# UC3844_-_CON_TEST.net
KiCad netlist of a schematic drawn in Altium Designer
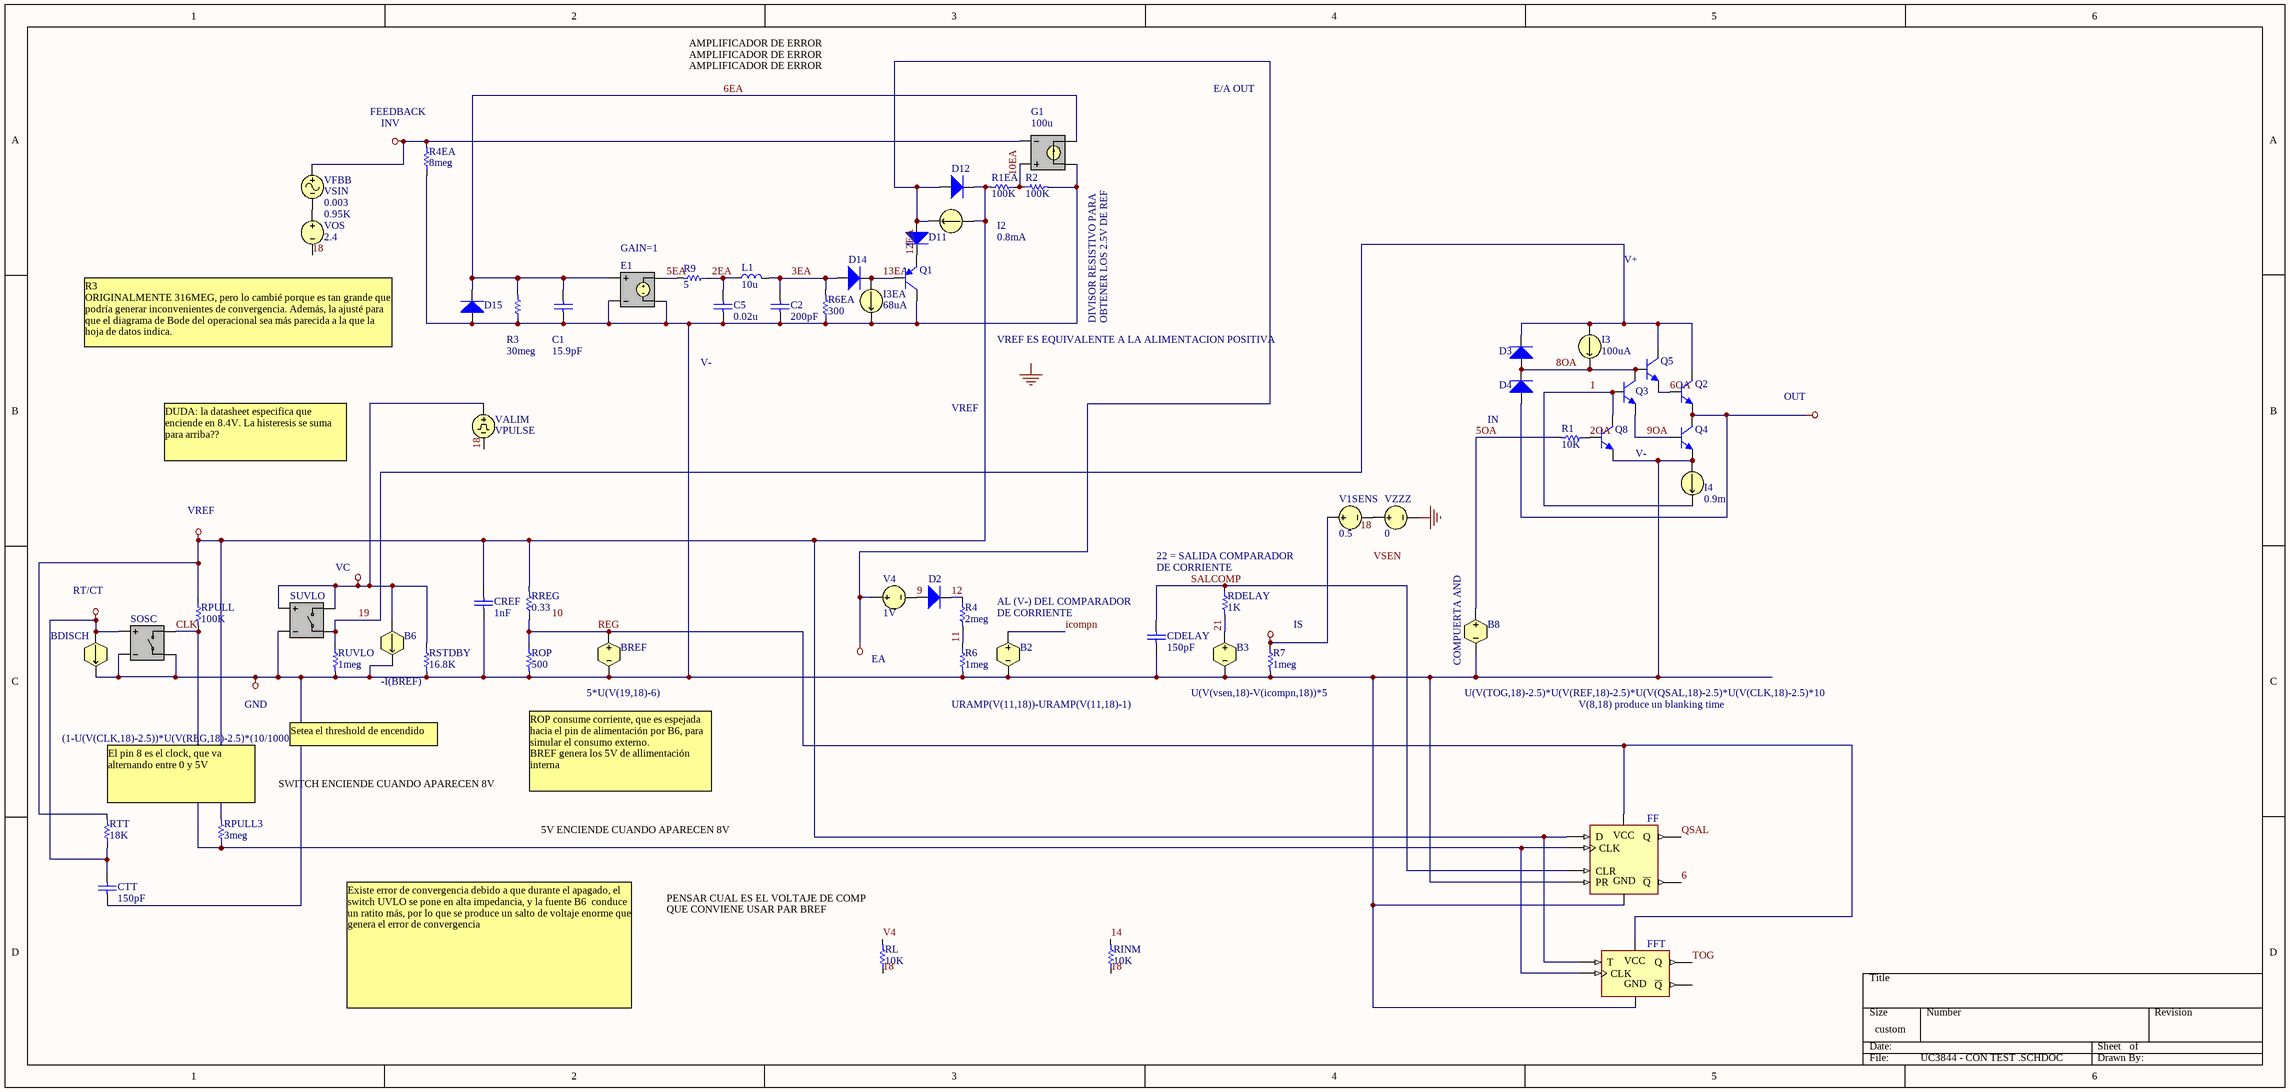
[diagram p0: UC3844 - CON TEST .SCHDOC]

(export (version "E")
  (design (tool "Eeschema 10.0.6"))
  (components
    (comp (ref "B2")
      (value "BVSRC")
      (description "Non-Linear Dependent Voltage Source")
      (fields
        (field (name "EQUATION") "URAMP(V(11,18))-URAMP(V(11,18)-1)")
        (field (name "PUBLISHER") "Altium Limited")
      )
      (libsource (lib "Simulation Sources") (part "BVSRC"))
    )
    (comp (ref "B3")
      (value "BVSRC")
      (description "Non-Linear Dependent Voltage Source")
      (fields
        (field (name "EQUATION") "U(V(vsen,18)-V(icompn,18))*5")
        (field (name "PUBLISHER") "Altium Limited")
      )
      (libsource (lib "Simulation Sources") (part "BVSRC"))
    )
    (comp (ref "B6")
      (value "BISRC")
      (description "Non-Linear Dependent Current Source")
      (fields (field (name "EQUATION") "-I(BREF)") (field (name "PUBLISHER") "Altium Limited"))
      (libsource (lib "Simulation Sources") (part "BISRC"))
    )
    (comp (ref "B8")
      (value "BVSRC")
      (description "Non-Linear Dependent Voltage Source")
      (fields
        (field (name "EQUATION") "U(V(TOG,18)-2.5)*U(V(REF,18)-2.5)*U(V(QSAL,18)-2.5)*U(V(CLK,18)-2.5)*10")
        (field (name "PUBLISHER") "Altium Limited")
      )
      (libsource (lib "Simulation Sources") (part "BVSRC"))
    )
    (comp (ref "BDISCH")
      (value "BISRC")
      (description "Non-Linear Dependent Current Source")
      (fields
        (field (name "EQUATION") "(1-U(V(CLK,18)-2.5))*U(V(REG,18)-2.5)*(10/1000)")
        (field (name "PUBLISHER") "Altium Limited")
      )
      (libsource (lib "Simulation Sources") (part "BISRC"))
    )
    (comp (ref "BREF")
      (value "BVSRC")
      (description "Non-Linear Dependent Voltage Source")
      (fields (field (name "EQUATION") "5*U(V(19,18)-6)") (field (name "PUBLISHER") "Altium Limited"))
      (libsource (lib "Simulation Sources") (part "BVSRC"))
    )
    (comp (ref "C1")
      (value "15.9pF")
      (footprint "0805")
      (description "Capacitor")
      (fields (field (name "VOLTAGE") "50V") (field (name "Comment") "Cap"))
      (libsource (lib "FEDE") (part "Cap"))
    )
    (comp (ref "C2")
      (value "200pF")
      (footprint "0805")
      (description "Capacitor")
      (fields (field (name "VOLTAGE") "50V") (field (name "Comment") "Cap"))
      (libsource (lib "FEDE") (part "Cap"))
    )
    (comp (ref "C5")
      (value "0.02u")
      (footprint "0805")
      (description "Capacitor")
      (fields (field (name "VOLTAGE") "50V") (field (name "Comment") "Cap"))
      (libsource (lib "FEDE") (part "Cap"))
    )
    (comp (ref "CDELAY")
      (value "150pF")
      (footprint "0805")
      (description "Capacitor")
      (fields (field (name "VOLTAGE") "50V") (field (name "Comment") "Cap"))
      (libsource (lib "FEDE") (part "Cap"))
    )
    (comp (ref "CREF")
      (value "1nF")
      (footprint "0805")
      (description "Capacitor")
      (fields (field (name "VOLTAGE") "50V") (field (name "Comment") "Cap"))
      (libsource (lib "FEDE") (part "Cap"))
    )
    (comp (ref "CTT")
      (value "150pF")
      (footprint "0805")
      (description "Capacitor")
      (fields (field (name "VOLTAGE") "50V") (field (name "Comment") "Cap"))
      (libsource (lib "FEDE") (part "Cap"))
    )
    (comp (ref "D2")
      (value "Diode")
      (footprint "diode400")
      (description "Diodo")
      (libsource (lib "FEDE") (part "Diode"))
    )
    (comp (ref "D3")
      (value "Diode")
      (footprint "diode400")
      (description "Diodo")
      (libsource (lib "FEDE") (part "Diode"))
    )
    (comp (ref "D4")
      (value "Diode")
      (footprint "diode400")
      (description "Diodo")
      (libsource (lib "FEDE") (part "Diode"))
    )
    (comp (ref "D11")
      (value "Diode")
      (footprint "diode400")
      (description "Diodo")
      (libsource (lib "FEDE") (part "Diode"))
    )
    (comp (ref "D12")
      (value "Diode")
      (footprint "diode400")
      (description "Diodo")
      (libsource (lib "FEDE") (part "Diode"))
    )
    (comp (ref "D14")
      (value "Diode")
      (footprint "diode400")
      (description "Diodo")
      (libsource (lib "FEDE") (part "Diode"))
    )
    (comp (ref "D15")
      (value "Diode")
      (footprint "diode400")
      (description "Diodo")
      (libsource (lib "FEDE") (part "Diode"))
    )
    (comp (ref "E1")
      (value "ESRC")
      (description "Voltage Controlled Voltage Source")
      (fields (field (name "PUBLISHER") "Altium Limited"))
      (libsource (lib "Simulation Sources") (part "ESRC"))
    )
    (comp (ref "FF")
      (value "FFSRV2")
      (description "D-Type Positive-Edge-Triggered Flip-Flop with Clear and Preset (simulación)")
      (libsource (lib "FEDE") (part "FFSRV2"))
    )
    (comp (ref "FFT")
      (value "FFT")
      (description "Positive-Edge-Triggered Flip-Flop T (simulación)")
      (libsource (lib "FEDE") (part "FFT"))
    )
    (comp (ref "G1")
      (value "GSRC")
      (description "Voltage Controlled Current Source")
      (fields (field (name "GAIN") "100u") (field (name "PUBLISHER") "Altium Limited"))
      (libsource (lib "Simulation Sources") (part "GSRC"))
    )
    (comp (ref "I2")
      (value "0.8mA")
      (description "Current Source")
      (fields (field (name "Comment") "ISRC") (field (name "PUBLISHER") "Altium Limited"))
      (libsource (lib "Simulation Sources") (part "ISRC"))
    )
    (comp (ref "I3")
      (value "100uA")
      (description "Current Source")
      (fields (field (name "Comment") "ISRC") (field (name "PUBLISHER") "Altium Limited"))
      (libsource (lib "Simulation Sources") (part "ISRC"))
    )
    (comp (ref "I3EA")
      (value "68uA")
      (description "Current Source")
      (fields (field (name "Comment") "ISRC") (field (name "PUBLISHER") "Altium Limited"))
      (libsource (lib "Simulation Sources") (part "ISRC"))
    )
    (comp (ref "I4")
      (value "0.9m")
      (description "Current Source")
      (fields (field (name "Comment") "ISRC") (field (name "PUBLISHER") "Altium Limited"))
      (libsource (lib "Simulation Sources") (part "ISRC"))
    )
    (comp (ref "L1")
      (value "10u")
      (footprint "TOROIDE TN14-9-5")
      (description "Inductor")
      (fields (field (name "Comment") "Inductor2"))
      (libsource (lib "FEDE") (part "Inductor2"))
    )
    (comp (ref "Q1")
      (value "PNP")
      (footprint "SOT23")
      (description "PNP Bipolar Transistor")
      (libsource (lib "FEDE") (part "PNP"))
    )
    (comp (ref "Q2")
      (value "NPN")
      (footprint "SOT23")
      (description "NPN Bipolar Transistor")
      (libsource (lib "FEDE") (part "NPN"))
    )
    (comp (ref "Q3")
      (value "NPN")
      (footprint "SOT23")
      (description "NPN Bipolar Transistor")
      (libsource (lib "FEDE") (part "NPN"))
    )
    (comp (ref "Q4")
      (value "NPN")
      (footprint "SOT23")
      (description "NPN Bipolar Transistor")
      (libsource (lib "FEDE") (part "NPN"))
    )
    (comp (ref "Q5")
      (value "NPN")
      (footprint "SOT23")
      (description "NPN Bipolar Transistor")
      (libsource (lib "FEDE") (part "NPN"))
    )
    (comp (ref "Q8")
      (value "NPN")
      (footprint "SOT23")
      (description "NPN Bipolar Transistor")
      (libsource (lib "FEDE") (part "NPN"))
    )
    (comp (ref "R1")
      (value "10K")
      (footprint "0805")
      (description "Resistor")
      (fields (field (name "POWER") "0.25W") (field (name "Comment") "Res"))
      (libsource (lib "FEDE") (part "Res"))
    )
    (comp (ref "R1EA")
      (value "100K")
      (footprint "0805")
      (description "Resistor")
      (fields (field (name "POWER") "0.25W") (field (name "Comment") "Res"))
      (libsource (lib "FEDE") (part "Res"))
    )
    (comp (ref "R2")
      (value "100K")
      (footprint "0805")
      (description "Resistor")
      (fields (field (name "POWER") "0.25W") (field (name "Comment") "Res"))
      (libsource (lib "FEDE") (part "Res"))
    )
    (comp (ref "R3")
      (value "30meg")
      (footprint "0805")
      (description "Resistor")
      (fields (field (name "POWER") "0.25W") (field (name "Comment") "Res"))
      (libsource (lib "FEDE") (part "Res"))
    )
    (comp (ref "R4")
      (value "2meg")
      (footprint "0805")
      (description "Resistor")
      (fields (field (name "POWER") "0.25W") (field (name "Comment") "Res"))
      (libsource (lib "FEDE") (part "Res"))
    )
    (comp (ref "R4EA")
      (value "8meg")
      (footprint "0805")
      (description "Resistor")
      (fields (field (name "POWER") "0.25W") (field (name "Comment") "Res"))
      (libsource (lib "FEDE") (part "Res"))
    )
    (comp (ref "R6")
      (value "1meg")
      (footprint "0805")
      (description "Resistor")
      (fields (field (name "POWER") "0.25W") (field (name "Comment") "Res"))
      (libsource (lib "FEDE") (part "Res"))
    )
    (comp (ref "R6EA")
      (value "300")
      (footprint "0805")
      (description "Resistor")
      (fields (field (name "POWER") "0.25W") (field (name "Comment") "Res"))
      (libsource (lib "FEDE") (part "Res"))
    )
    (comp (ref "R7")
      (value "1meg")
      (footprint "0805")
      (description "Resistor")
      (fields (field (name "POWER") "0.25W") (field (name "Comment") "Res"))
      (libsource (lib "FEDE") (part "Res"))
    )
    (comp (ref "R9")
      (value "5")
      (footprint "0805")
      (description "Resistor")
      (fields (field (name "POWER") "0.25W") (field (name "Comment") "Res"))
      (libsource (lib "FEDE") (part "Res"))
    )
    (comp (ref "RDELAY")
      (value "1K")
      (footprint "0805")
      (description "Resistor")
      (fields (field (name "POWER") "0.25W") (field (name "Comment") "Res"))
      (libsource (lib "FEDE") (part "Res"))
    )
    (comp (ref "RINM")
      (value "10K")
      (footprint "0805")
      (description "Resistor")
      (fields (field (name "POWER") "0.25W") (field (name "Comment") "Res"))
      (libsource (lib "FEDE") (part "Res"))
    )
    (comp (ref "RL")
      (value "10K")
      (footprint "0805")
      (description "Resistor")
      (fields (field (name "POWER") "0.25W") (field (name "Comment") "Res"))
      (libsource (lib "FEDE") (part "Res"))
    )
    (comp (ref "ROP")
      (value "500")
      (footprint "0805")
      (description "Resistor")
      (fields (field (name "POWER") "0.25W") (field (name "Comment") "Res"))
      (libsource (lib "FEDE") (part "Res"))
    )
    (comp (ref "RPULL")
      (value "100K")
      (footprint "0805")
      (description "Resistor")
      (fields (field (name "POWER") "0.25W") (field (name "Comment") "Res"))
      (libsource (lib "FEDE") (part "Res"))
    )
    (comp (ref "RPULL3")
      (value "3meg")
      (footprint "0805")
      (description "Resistor")
      (fields (field (name "POWER") "0.25W") (field (name "Comment") "Res"))
      (libsource (lib "FEDE") (part "Res"))
    )
    (comp (ref "RREG")
      (value "0.33")
      (footprint "0805")
      (description "Resistor")
      (fields (field (name "POWER") "0.25W") (field (name "Comment") "Res"))
      (libsource (lib "FEDE") (part "Res"))
    )
    (comp (ref "RSTDBY")
      (value "16.8K")
      (footprint "0805")
      (description "Resistor")
      (fields (field (name "POWER") "0.25W") (field (name "Comment") "Res"))
      (libsource (lib "FEDE") (part "Res"))
    )
    (comp (ref "RTT")
      (value "18K")
      (footprint "0805")
      (description "Resistor")
      (fields (field (name "POWER") "0.25W") (field (name "Comment") "Res"))
      (libsource (lib "FEDE") (part "Res"))
    )
    (comp (ref "RUVLO")
      (value "1meg")
      (footprint "0805")
      (description "Resistor")
      (fields (field (name "POWER") "0.25W") (field (name "Comment") "Res"))
      (libsource (lib "FEDE") (part "Res"))
    )
    (comp (ref "SOSC")
      (value "VSW")
      (description "Voltage Controlled Switch (simulación)")
      (libsource (lib "FEDE") (part "VSW"))
    )
    (comp (ref "SUVLO")
      (value "VSW")
      (description "Voltage Controlled Switch (simulación)")
      (libsource (lib "FEDE") (part "VSW"))
    )
    (comp (ref "V1SENS")
      (value "0.5")
      (description "Voltage Source")
      (fields (field (name "Comment") "VSRC") (field (name "PUBLISHER") "Altium Limited"))
      (libsource (lib "Simulation Sources") (part "VSRC"))
    )
    (comp (ref "V4")
      (value "1V")
      (description "Voltage Source")
      (fields (field (name "Comment") "VSRC") (field (name "PUBLISHER") "Altium Limited"))
      (libsource (lib "Simulation Sources") (part "VSRC"))
    )
    (comp (ref "VALIM")
      (value "VPULSE")
      (description "Pulse Voltage Source")
      (fields (field (name "PUBLISHER") "Altium Limited"))
      (libsource (lib "Simulation Sources") (part "VPULSE"))
    )
    (comp (ref "VFBB")
      (value "VSIN")
      (description "Sinusoidal Voltage Source")
      (fields
        (field (name "AMPLITUDE") "0.003")
        (field (name "FREQUENCY") "0.95K")
        (field (name "PUBLISHER") "Altium Limited")
      )
      (libsource (lib "Simulation Sources") (part "VSIN"))
    )
    (comp (ref "VOS")
      (value "2.4")
      (description "Voltage Source")
      (fields (field (name "Comment") "VSRC") (field (name "PUBLISHER") "Altium Limited"))
      (libsource (lib "Simulation Sources") (part "VSRC"))
    )
    (comp (ref "VZZZ")
      (value "0")
      (description "Voltage Source")
      (fields (field (name "Comment") "VSRC") (field (name "PUBLISHER") "Altium Limited"))
      (libsource (lib "Simulation Sources") (part "VSRC"))
    )
  )
  (nets
    (net (code "1") (name "/1") (class "Default")
      (node (ref "I4") (pin "2") (pinfunction "2_2") (pintype "passive"))
      (node (ref "Q3") (pin "2") (pinfunction "B_2") (pintype "passive"))
      (node (ref "Q8") (pin "1") (pinfunction "C_1") (pintype "passive"))
    )
    (net (code "2") (name "/2EA") (class "Default")
      (node (ref "C5") (pin "2") (pinfunction "2_2") (pintype "passive"))
      (node (ref "L1") (pin "1") (pinfunction "1_1") (pintype "passive"))
      (node (ref "R9") (pin "1") (pinfunction "1_1") (pintype "passive"))
    )
    (net (code "3") (name "/2OA") (class "Default")
      (node (ref "Q8") (pin "2") (pinfunction "B_2") (pintype "passive"))
      (node (ref "R1") (pin "1") (pinfunction "1_1") (pintype "passive"))
    )
    (net (code "4") (name "/3EA") (class "Default")
      (node (ref "C2") (pin "2") (pinfunction "2_2") (pintype "passive"))
      (node (ref "D14") (pin "1") (pinfunction "1_1") (pintype "passive"))
      (node (ref "L1") (pin "2") (pinfunction "2_2") (pintype "passive"))
      (node (ref "R6EA") (pin "2") (pinfunction "2_2") (pintype "passive"))
    )
    (net (code "5") (name "/5EA") (class "Default")
      (node (ref "E1") (pin "3") (pinfunction "N+_3") (pintype "passive"))
      (node (ref "R9") (pin "2") (pinfunction "2_2") (pintype "passive"))
    )
    (net (code "6") (name "/5OA") (class "Default")
      (node (ref "B8") (pin "1") (pinfunction "1_1") (pintype "passive"))
      (node (ref "R1") (pin "2") (pinfunction "2_2") (pintype "passive"))
    )
    (net (code "7") (name "/6") (class "Default")
      (node (ref "FF") (pin "6") (pinfunction "~{Q}_6") (pintype "output"))
    )
    (net (code "8") (name "/6EA") (class "Default")
      (node (ref "C1") (pin "2") (pinfunction "2_2") (pintype "passive"))
      (node (ref "D15") (pin "2") (pinfunction "2_2") (pintype "passive"))
      (node (ref "E1") (pin "1") (pinfunction "NC+_1") (pintype "passive"))
      (node (ref "G1") (pin "4") (pinfunction "N-_4") (pintype "passive"))
      (node (ref "R3") (pin "2") (pinfunction "2_2") (pintype "passive"))
    )
    (net (code "9") (name "/6OA") (class "Default")
      (node (ref "Q2") (pin "2") (pinfunction "B_2") (pintype "passive"))
      (node (ref "Q5") (pin "3") (pinfunction "E_3") (pintype "passive"))
    )
    (net (code "10") (name "/8OA") (class "Default")
      (node (ref "D3") (pin "1") (pinfunction "1_1") (pintype "passive"))
      (node (ref "D4") (pin "2") (pinfunction "2_2") (pintype "passive"))
      (node (ref "I3") (pin "2") (pinfunction "2_2") (pintype "passive"))
      (node (ref "Q3") (pin "1") (pinfunction "C_1") (pintype "passive"))
      (node (ref "Q5") (pin "2") (pinfunction "B_2") (pintype "passive"))
    )
    (net (code "11") (name "/9") (class "Default")
      (node (ref "D2") (pin "1") (pinfunction "1_1") (pintype "passive"))
      (node (ref "V4") (pin "2") (pinfunction "2_2") (pintype "passive"))
    )
    (net (code "12") (name "/9OA") (class "Default")
      (node (ref "Q3") (pin "3") (pinfunction "E_3") (pintype "passive"))
      (node (ref "Q4") (pin "2") (pinfunction "B_2") (pintype "passive"))
    )
    (net (code "14") (name "/10EA") (class "Default")
      (node (ref "G1") (pin "1") (pinfunction "NC+_1") (pintype "passive"))
      (node (ref "R1EA") (pin "1") (pinfunction "1_1") (pintype "passive"))
      (node (ref "R2") (pin "1") (pinfunction "1_1") (pintype "passive"))
    )
    (net (code "15") (name "/11") (class "Default")
      (node (ref "R4") (pin "2") (pinfunction "2_2") (pintype "passive"))
      (node (ref "R6") (pin "1") (pinfunction "1_1") (pintype "passive"))
    )
    (net (code "16") (name "/12") (class "Default")
      (node (ref "D2") (pin "2") (pinfunction "2_2") (pintype "passive"))
      (node (ref "R4") (pin "1") (pinfunction "1_1") (pintype "passive"))
    )
    (net (code "17") (name "/12EA") (class "Default")
      (node (ref "D11") (pin "2") (pinfunction "2_2") (pintype "passive"))
      (node (ref "Q1") (pin "3") (pinfunction "E_3") (pintype "passive"))
    )
    (net (code "18") (name "/13EA") (class "Default")
      (node (ref "D14") (pin "2") (pinfunction "2_2") (pintype "passive"))
      (node (ref "I3EA") (pin "1") (pinfunction "1_1") (pintype "passive"))
      (node (ref "Q1") (pin "2") (pinfunction "B_2") (pintype "passive"))
    )
    (net (code "19") (name "/14") (class "Default")
      (node (ref "RINM") (pin "2") (pinfunction "2_2") (pintype "passive"))
    )
    (net (code "20") (name "/19") (class "Default")
      (node (ref "D3") (pin "2") (pinfunction "2_2") (pintype "passive"))
      (node (ref "I3") (pin "1") (pinfunction "1_1") (pintype "passive"))
      (node (ref "Q2") (pin "1") (pinfunction "C_1") (pintype "passive"))
      (node (ref "Q5") (pin "1") (pinfunction "C_1") (pintype "passive"))
      (node (ref "RUVLO") (pin "1") (pinfunction "1_1") (pintype "passive"))
      (node (ref "SUVLO") (pin "4") (pinfunction "N2-_4") (pintype "passive"))
    )
    (net (code "21") (name "/21") (class "Default")
      (node (ref "B3") (pin "1") (pinfunction "1_1") (pintype "passive"))
      (node (ref "RDELAY") (pin "2") (pinfunction "2_2") (pintype "passive"))
    )
    (net (code "22") (name "/CLK") (class "Default")
      (node (ref "FF") (pin "3") (pinfunction "CLK_3") (pintype "input"))
      (node (ref "FFT") (pin "2") (pinfunction "CLK_2") (pintype "input"))
      (node (ref "RPULL") (pin "2") (pinfunction "2_2") (pintype "passive"))
      (node (ref "RPULL3") (pin "1") (pinfunction "1_1") (pintype "passive"))
      (node (ref "SOSC") (pin "3") (pinfunction "N2+_3") (pintype "passive"))
    )
    (net (code "23") (name "/QSAL") (class "Default")
      (node (ref "FF") (pin "5") (pinfunction "Q_5") (pintype "output"))
    )
    (net (code "24") (name "/REG") (class "Default")
      (node (ref "BREF") (pin "1") (pinfunction "1_1") (pintype "passive"))
      (node (ref "FF") (pin "14") (pinfunction "VCC_14") (pintype "power_in"))
      (node (ref "FFT") (pin "5") (pinfunction "VCC_5") (pintype "power_in"))
      (node (ref "ROP") (pin "1") (pinfunction "1_1") (pintype "passive"))
      (node (ref "RREG") (pin "1") (pinfunction "1_1") (pintype "passive"))
    )
    (net (code "25") (name "/SALCOMP") (class "Default")
      (node (ref "CDELAY") (pin "2") (pinfunction "2_2") (pintype "passive"))
      (node (ref "FF") (pin "1") (pinfunction "CLR_1") (pintype "input"))
      (node (ref "RDELAY") (pin "1") (pinfunction "1_1") (pintype "passive"))
    )
    (net (code "26") (name "/TOG") (class "Default")
      (node (ref "FFT") (pin "3") (pinfunction "Q_3") (pintype "output"))
    )
    (net (code "27") (name "/V4") (class "Default")
      (node (ref "RL") (pin "2") (pinfunction "2_2") (pintype "passive"))
    )
    (net (code "28") (name "/icompn") (class "Default")
      (node (ref "B2") (pin "1") (pinfunction "1_1") (pintype "passive"))
    )
    (net (code "29") (name "18") (class "Default")
      (node (ref "B2") (pin "2") (pinfunction "2_2") (pintype "passive"))
      (node (ref "B3") (pin "2") (pinfunction "2_2") (pintype "passive"))
      (node (ref "B6") (pin "2") (pinfunction "2_2") (pintype "passive"))
      (node (ref "B8") (pin "2") (pinfunction "2_2") (pintype "passive"))
      (node (ref "BDISCH") (pin "2") (pinfunction "2_2") (pintype "passive"))
      (node (ref "BREF") (pin "2") (pinfunction "2_2") (pintype "passive"))
      (node (ref "C1") (pin "1") (pinfunction "1_1") (pintype "passive"))
      (node (ref "C2") (pin "1") (pinfunction "1_1") (pintype "passive"))
      (node (ref "C5") (pin "1") (pinfunction "1_1") (pintype "passive"))
      (node (ref "CDELAY") (pin "1") (pinfunction "1_1") (pintype "passive"))
      (node (ref "CREF") (pin "1") (pinfunction "1_1") (pintype "passive"))
      (node (ref "CTT") (pin "1") (pinfunction "1_1") (pintype "passive"))
      (node (ref "D15") (pin "1") (pinfunction "1_1") (pintype "passive"))
      (node (ref "E1") (pin "2") (pinfunction "NC-_2") (pintype "passive"))
      (node (ref "E1") (pin "4") (pinfunction "N-_4") (pintype "passive"))
      (node (ref "FF") (pin "4") (pinfunction "PR_4") (pintype "input"))
      (node (ref "FF") (pin "7") (pinfunction "GND_7") (pintype "power_in"))
      (node (ref "FFT") (pin "6") (pinfunction "GND_6") (pintype "power_in"))
      (node (ref "G1") (pin "3") (pinfunction "N+_3") (pintype "passive"))
      (node (ref "I3EA") (pin "2") (pinfunction "2_2") (pintype "passive"))
      (node (ref "I4") (pin "1") (pinfunction "1_1") (pintype "passive"))
      (node (ref "Q1") (pin "1") (pinfunction "C_1") (pintype "passive"))
      (node (ref "Q4") (pin "3") (pinfunction "E_3") (pintype "passive"))
      (node (ref "Q8") (pin "3") (pinfunction "E_3") (pintype "passive"))
      (node (ref "R2") (pin "2") (pinfunction "2_2") (pintype "passive"))
      (node (ref "R3") (pin "1") (pinfunction "1_1") (pintype "passive"))
      (node (ref "R4EA") (pin "1") (pinfunction "1_1") (pintype "passive"))
      (node (ref "R6") (pin "2") (pinfunction "2_2") (pintype "passive"))
      (node (ref "R6EA") (pin "1") (pinfunction "1_1") (pintype "passive"))
      (node (ref "R7") (pin "2") (pinfunction "2_2") (pintype "passive"))
      (node (ref "RINM") (pin "1") (pinfunction "1_1") (pintype "passive"))
      (node (ref "RL") (pin "1") (pinfunction "1_1") (pintype "passive"))
      (node (ref "ROP") (pin "2") (pinfunction "2_2") (pintype "passive"))
      (node (ref "RSTDBY") (pin "2") (pinfunction "2_2") (pintype "passive"))
      (node (ref "RUVLO") (pin "2") (pinfunction "2_2") (pintype "passive"))
      (node (ref "SOSC") (pin "2") (pinfunction "N1-_2") (pintype "passive"))
      (node (ref "SOSC") (pin "4") (pinfunction "N2-_4") (pintype "passive"))
      (node (ref "SUVLO") (pin "2") (pinfunction "N1-_2") (pintype "passive"))
      (node (ref "V1SENS") (pin "2") (pinfunction "2_2") (pintype "passive"))
      (node (ref "VALIM") (pin "2") (pinfunction "2_2") (pintype "passive"))
      (node (ref "VOS") (pin "2") (pinfunction "2_2") (pintype "passive"))
      (node (ref "VZZZ") (pin "1") (pinfunction "1_1") (pintype "passive"))
    )
    (net (code "30") (name "ALIM") (class "Default")
      (node (ref "B6") (pin "1") (pinfunction "1_1") (pintype "passive"))
      (node (ref "RSTDBY") (pin "1") (pinfunction "1_1") (pintype "passive"))
      (node (ref "SUVLO") (pin "1") (pinfunction "N1+_1") (pintype "passive"))
      (node (ref "SUVLO") (pin "3") (pinfunction "N2+_3") (pintype "passive"))
      (node (ref "VALIM") (pin "1") (pinfunction "1_1") (pintype "passive"))
    )
    (net (code "31") (name "EAOUT") (class "Default")
      (node (ref "D11") (pin "1") (pinfunction "1_1") (pintype "passive"))
      (node (ref "D12") (pin "1") (pinfunction "1_1") (pintype "passive"))
      (node (ref "I2") (pin "2") (pinfunction "2_2") (pintype "passive"))
      (node (ref "V4") (pin "1") (pinfunction "1_1") (pintype "passive"))
    )
    (net (code "32") (name "FEED") (class "Default")
      (node (ref "G1") (pin "2") (pinfunction "NC-_2") (pintype "passive"))
      (node (ref "R4EA") (pin "2") (pinfunction "2_2") (pintype "passive"))
      (node (ref "VFBB") (pin "1") (pinfunction "1_1") (pintype "passive"))
    )
    (net (code "33") (name "GND") (class "Default")
      (node (ref "VZZZ") (pin "2") (pinfunction "2_2") (pintype "passive"))
    )
    (net (code "34") (name "Net-(VFBB-Pad2)") (class "Default")
      (node (ref "VFBB") (pin "2") (pinfunction "2_2") (pintype "passive"))
      (node (ref "VOS") (pin "1") (pinfunction "1_1") (pintype "passive"))
    )
    (net (code "35") (name "OUT") (class "Default")
      (node (ref "D4") (pin "1") (pinfunction "1_1") (pintype "passive"))
      (node (ref "Q2") (pin "3") (pinfunction "E_3") (pintype "passive"))
      (node (ref "Q4") (pin "1") (pinfunction "C_1") (pintype "passive"))
    )
    (net (code "36") (name "REF") (class "Default")
      (node (ref "CREF") (pin "2") (pinfunction "2_2") (pintype "passive"))
      (node (ref "D12") (pin "2") (pinfunction "2_2") (pintype "passive"))
      (node (ref "FF") (pin "2") (pinfunction "D_2") (pintype "input"))
      (node (ref "FFT") (pin "1") (pinfunction "T_1") (pintype "input"))
      (node (ref "I2") (pin "1") (pinfunction "1_1") (pintype "passive"))
      (node (ref "R1EA") (pin "2") (pinfunction "2_2") (pintype "passive"))
      (node (ref "RPULL") (pin "1") (pinfunction "1_1") (pintype "passive"))
      (node (ref "RPULL3") (pin "2") (pinfunction "2_2") (pintype "passive"))
      (node (ref "RREG") (pin "2") (pinfunction "2_2") (pintype "passive"))
      (node (ref "RTT") (pin "2") (pinfunction "2_2") (pintype "passive"))
    )
    (net (code "37") (name "RTCT") (class "Default")
      (node (ref "BDISCH") (pin "1") (pinfunction "1_1") (pintype "passive"))
      (node (ref "CTT") (pin "2") (pinfunction "2_2") (pintype "passive"))
      (node (ref "RTT") (pin "1") (pinfunction "1_1") (pintype "passive"))
      (node (ref "SOSC") (pin "1") (pinfunction "N1+_1") (pintype "passive"))
    )
    (net (code "38") (name "VSEN") (class "Default")
      (node (ref "R7") (pin "1") (pinfunction "1_1") (pintype "passive"))
      (node (ref "V1SENS") (pin "1") (pinfunction "1_1") (pintype "passive"))
    )
    (net (code "39") (name "unconnected-(FFT-~{Q}-Pad4)") (class "Default")
      (node (ref "FFT") (pin "4") (pinfunction "~{Q}_4") (pintype "output"))
    )
  )
)
